# SCH_Base-robot_2026-06-24.net
KiCad netlist of a schematic drawn in EasyEDA
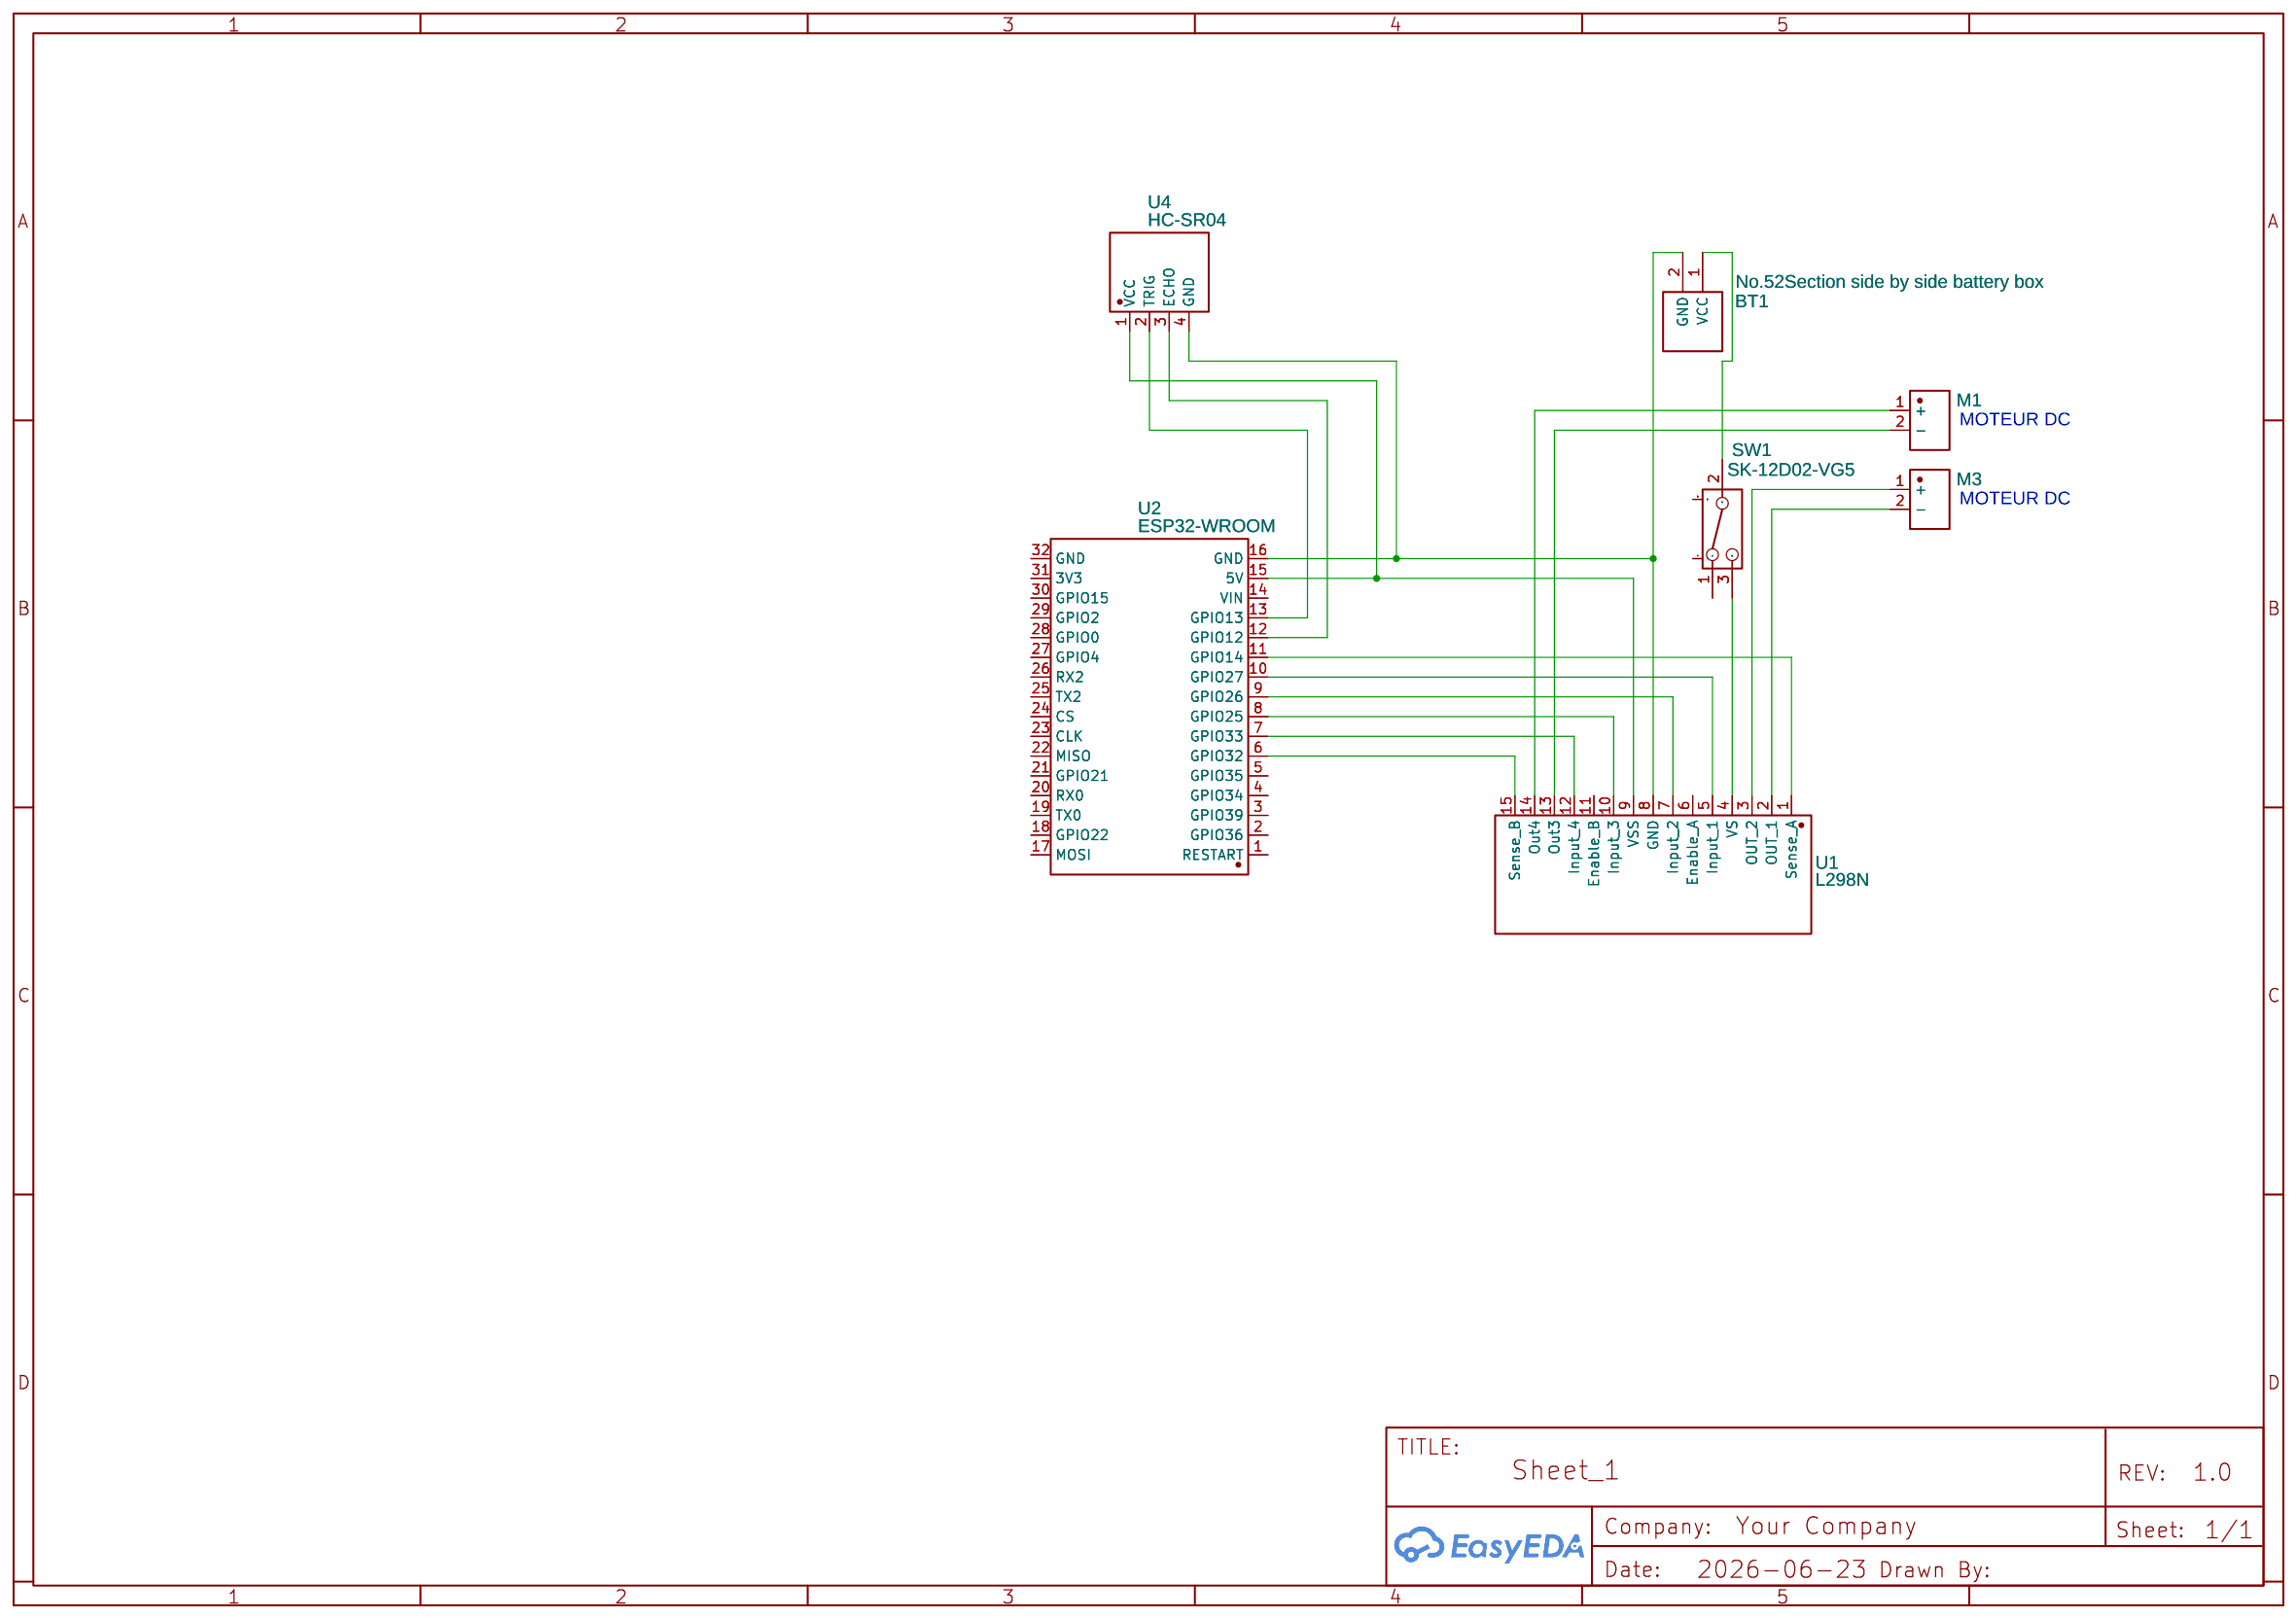
[diagram p0: schematic sheet]

(export (version "E")
  (design (tool "Eeschema 10.0.6"))
  (components
    (comp (ref "BT1")
      (value "No.52Section side by side battery box")
      (fields (field (name "Manufacturer Part") "五号2节并列电池盒") (field (name "Manufacturer") "国产"))
      (libsource (lib "") (part "No.52Section side by side battery box"))
    )
    (comp (ref "M1")
      (value "MOTEUR DC")
      (fields (field (name "Manufacturer Part") "Z4TH3B0791626") (field (name "Manufacturer") "KOTL(金龙机电)"))
      (libsource (lib "") (part "Z4TH3B0791626"))
    )
    (comp (ref "M3")
      (value "MOTEUR DC")
      (fields (field (name "Manufacturer Part") "Z4TH3B0791626") (field (name "Manufacturer") "KOTL(金龙机电)"))
      (libsource (lib "") (part "Z4TH3B0791626"))
    )
    (comp (ref "SW1")
      (value "SK-12D02-VG5")
      (fields (field (name "Manufacturer") "Rectangular Connectors - Contacts"))
      (libsource (lib "") (part "SK-12D02-VG5"))
    )
    (comp (ref "U1")
      (value "L298N")
      (fields (field (name "Manufacturer") "HGSEMI(华冠)"))
      (libsource (lib "") (part "L298N"))
    )
    (comp (ref "U2")
      (value "ESP32-WROOM")
      (fields (field (name "Manufacturer Part") "ESP32-WROOM-32U(16MB)"))
      (libsource (lib "") (part "ESP32-WROOM"))
    )
    (comp (ref "U4")
      (value "HC-SR04")
      (fields (field (name "Manufacturer") "Universal Microelectronics"))
      (libsource (lib "") (part "HC-SR04"))
    )
  )
  (nets
    (net (code "1") (name "Net-(BT1-GND)") (class "Default")
      (node (ref "BT1") (pin "2") (pinfunction "GND_2") (pintype "unspecified"))
      (node (ref "U1") (pin "8") (pinfunction "GND_8") (pintype "unspecified"))
      (node (ref "U2") (pin "16") (pinfunction "GND_16") (pintype "unspecified"))
      (node (ref "U4") (pin "4") (pinfunction "GND_4") (pintype "unspecified"))
    )
    (net (code "2") (name "Net-(BT1-VCC)") (class "Default")
      (node (ref "BT1") (pin "1") (pinfunction "VCC_1") (pintype "unspecified"))
      (node (ref "SW1") (pin "2") (pinfunction "2_2") (pintype "unspecified"))
    )
    (net (code "3") (name "Net-(M1-+)") (class "Default")
      (node (ref "M1") (pin "1") (pinfunction "+_1") (pintype "unspecified"))
      (node (ref "U1") (pin "14") (pinfunction "Out4_14") (pintype "unspecified"))
    )
    (net (code "4") (name "Net-(M1--)") (class "Default")
      (node (ref "M1") (pin "2") (pinfunction "-_2") (pintype "unspecified"))
      (node (ref "U1") (pin "13") (pinfunction "Out3_13") (pintype "unspecified"))
    )
    (net (code "5") (name "Net-(M3-+)") (class "Default")
      (node (ref "M3") (pin "1") (pinfunction "+_1") (pintype "unspecified"))
      (node (ref "U1") (pin "3") (pinfunction "OUT_2_3") (pintype "unspecified"))
    )
    (net (code "6") (name "Net-(M3--)") (class "Default")
      (node (ref "M3") (pin "2") (pinfunction "-_2") (pintype "unspecified"))
      (node (ref "U1") (pin "2") (pinfunction "OUT_1_2") (pintype "unspecified"))
    )
    (net (code "7") (name "Net-(U1-Input_1)") (class "Default")
      (node (ref "U1") (pin "5") (pinfunction "Input_1_5") (pintype "unspecified"))
      (node (ref "U2") (pin "10") (pinfunction "GPIO27_10") (pintype "unspecified"))
    )
    (net (code "8") (name "Net-(U1-Input_2)") (class "Default")
      (node (ref "U1") (pin "7") (pinfunction "Input_2_7") (pintype "unspecified"))
      (node (ref "U2") (pin "9") (pinfunction "GPIO26_9") (pintype "unspecified"))
    )
    (net (code "9") (name "Net-(U1-Input_3)") (class "Default")
      (node (ref "U1") (pin "10") (pinfunction "Input_3_10") (pintype "unspecified"))
      (node (ref "U2") (pin "8") (pinfunction "GPIO25_8") (pintype "unspecified"))
    )
    (net (code "10") (name "Net-(U1-Input_4)") (class "Default")
      (node (ref "U1") (pin "12") (pinfunction "Input_4_12") (pintype "unspecified"))
      (node (ref "U2") (pin "7") (pinfunction "GPIO33_7") (pintype "unspecified"))
    )
    (net (code "11") (name "Net-(U1-Sense_A)") (class "Default")
      (node (ref "U1") (pin "1") (pinfunction "Sense_A_1") (pintype "unspecified"))
      (node (ref "U2") (pin "11") (pinfunction "GPIO14_11") (pintype "unspecified"))
    )
    (net (code "12") (name "Net-(U1-Sense_B)") (class "Default")
      (node (ref "U1") (pin "15") (pinfunction "Sense_B_15") (pintype "unspecified"))
      (node (ref "U2") (pin "6") (pinfunction "GPIO32_6") (pintype "unspecified"))
    )
    (net (code "13") (name "Net-(U1-VS)") (class "Default")
      (node (ref "SW1") (pin "3") (pinfunction "3_3") (pintype "unspecified"))
      (node (ref "U1") (pin "4") (pinfunction "VS_4") (pintype "unspecified"))
    )
    (net (code "14") (name "Net-(U1-VSS)") (class "Default")
      (node (ref "U1") (pin "9") (pinfunction "VSS_9") (pintype "unspecified"))
      (node (ref "U2") (pin "15") (pinfunction "5V_15") (pintype "unspecified"))
      (node (ref "U4") (pin "1") (pinfunction "VCC_1") (pintype "unspecified"))
    )
    (net (code "15") (name "Net-(U2-GPIO12)") (class "Default")
      (node (ref "U2") (pin "12") (pinfunction "GPIO12_12") (pintype "unspecified"))
      (node (ref "U4") (pin "3") (pinfunction "ECHO_3") (pintype "unspecified"))
    )
    (net (code "16") (name "Net-(U2-GPIO13)") (class "Default")
      (node (ref "U2") (pin "13") (pinfunction "GPIO13_13") (pintype "unspecified"))
      (node (ref "U4") (pin "2") (pinfunction "TRIG_2") (pintype "unspecified"))
    )
    (net (code "17") (name "unconnected-(SW1-Pad1)") (class "Default")
      (node (ref "SW1") (pin "1") (pinfunction "1_1") (pintype "unspecified"))
    )
    (net (code "18") (name "unconnected-(SW1-Pad4)") (class "Default")
      (node (ref "SW1") (pin "4") (pinfunction "4_4") (pintype "unspecified"))
    )
    (net (code "19") (name "unconnected-(SW1-Pad5)") (class "Default")
      (node (ref "SW1") (pin "5") (pinfunction "5_5") (pintype "unspecified"))
    )
    (net (code "20") (name "unconnected-(U1-Enable_A-Pad6)") (class "Default")
      (node (ref "U1") (pin "6") (pinfunction "Enable_A_6") (pintype "unspecified"))
    )
    (net (code "21") (name "unconnected-(U1-Enable_B-Pad11)") (class "Default")
      (node (ref "U1") (pin "11") (pinfunction "Enable_B_11") (pintype "unspecified"))
    )
    (net (code "22") (name "unconnected-(U2-3V3-Pad31)") (class "Default")
      (node (ref "U2") (pin "31") (pinfunction "3V3_31") (pintype "unspecified"))
    )
    (net (code "23") (name "unconnected-(U2-CLK-Pad23)") (class "Default")
      (node (ref "U2") (pin "23") (pinfunction "CLK_23") (pintype "unspecified"))
    )
    (net (code "24") (name "unconnected-(U2-CS-Pad24)") (class "Default")
      (node (ref "U2") (pin "24") (pinfunction "CS_24") (pintype "unspecified"))
    )
    (net (code "25") (name "unconnected-(U2-GND-Pad32)") (class "Default")
      (node (ref "U2") (pin "32") (pinfunction "GND_32") (pintype "unspecified"))
    )
    (net (code "26") (name "unconnected-(U2-GPIO0-Pad28)") (class "Default")
      (node (ref "U2") (pin "28") (pinfunction "GPIO0_28") (pintype "unspecified"))
    )
    (net (code "27") (name "unconnected-(U2-GPIO2-Pad29)") (class "Default")
      (node (ref "U2") (pin "29") (pinfunction "GPIO2_29") (pintype "unspecified"))
    )
    (net (code "28") (name "unconnected-(U2-GPIO4-Pad27)") (class "Default")
      (node (ref "U2") (pin "27") (pinfunction "GPIO4_27") (pintype "unspecified"))
    )
    (net (code "29") (name "unconnected-(U2-GPIO15-Pad30)") (class "Default")
      (node (ref "U2") (pin "30") (pinfunction "GPIO15_30") (pintype "unspecified"))
    )
    (net (code "30") (name "unconnected-(U2-GPIO21-Pad21)") (class "Default")
      (node (ref "U2") (pin "21") (pinfunction "GPIO21_21") (pintype "unspecified"))
    )
    (net (code "31") (name "unconnected-(U2-GPIO22-Pad18)") (class "Default")
      (node (ref "U2") (pin "18") (pinfunction "GPIO22_18") (pintype "unspecified"))
    )
    (net (code "32") (name "unconnected-(U2-GPIO34-Pad4)") (class "Default")
      (node (ref "U2") (pin "4") (pinfunction "GPIO34_4") (pintype "unspecified"))
    )
    (net (code "33") (name "unconnected-(U2-GPIO35-Pad5)") (class "Default")
      (node (ref "U2") (pin "5") (pinfunction "GPIO35_5") (pintype "unspecified"))
    )
    (net (code "34") (name "unconnected-(U2-GPIO36-Pad2)") (class "Default")
      (node (ref "U2") (pin "2") (pinfunction "GPIO36_2") (pintype "unspecified"))
    )
    (net (code "35") (name "unconnected-(U2-GPIO39-Pad3)") (class "Default")
      (node (ref "U2") (pin "3") (pinfunction "GPIO39_3") (pintype "unspecified"))
    )
    (net (code "36") (name "unconnected-(U2-MISO-Pad22)") (class "Default")
      (node (ref "U2") (pin "22") (pinfunction "MISO_22") (pintype "unspecified"))
    )
    (net (code "37") (name "unconnected-(U2-MOSI-Pad17)") (class "Default")
      (node (ref "U2") (pin "17") (pinfunction "MOSI_17") (pintype "unspecified"))
    )
    (net (code "38") (name "unconnected-(U2-RESTART-Pad1)") (class "Default")
      (node (ref "U2") (pin "1") (pinfunction "RESTART_1") (pintype "unspecified"))
    )
    (net (code "39") (name "unconnected-(U2-RX0-Pad20)") (class "Default")
      (node (ref "U2") (pin "20") (pinfunction "RX0_20") (pintype "unspecified"))
    )
    (net (code "40") (name "unconnected-(U2-RX2-Pad26)") (class "Default")
      (node (ref "U2") (pin "26") (pinfunction "RX2_26") (pintype "unspecified"))
    )
    (net (code "41") (name "unconnected-(U2-TX0-Pad19)") (class "Default")
      (node (ref "U2") (pin "19") (pinfunction "TX0_19") (pintype "unspecified"))
    )
    (net (code "42") (name "unconnected-(U2-TX2-Pad25)") (class "Default")
      (node (ref "U2") (pin "25") (pinfunction "TX2_25") (pintype "unspecified"))
    )
    (net (code "43") (name "unconnected-(U2-VIN-Pad14)") (class "Default")
      (node (ref "U2") (pin "14") (pinfunction "VIN_14") (pintype "unspecified"))
    )
  )
)
